# LightsDriver.net
KiCad netlist of a schematic drawn in Altium Designer
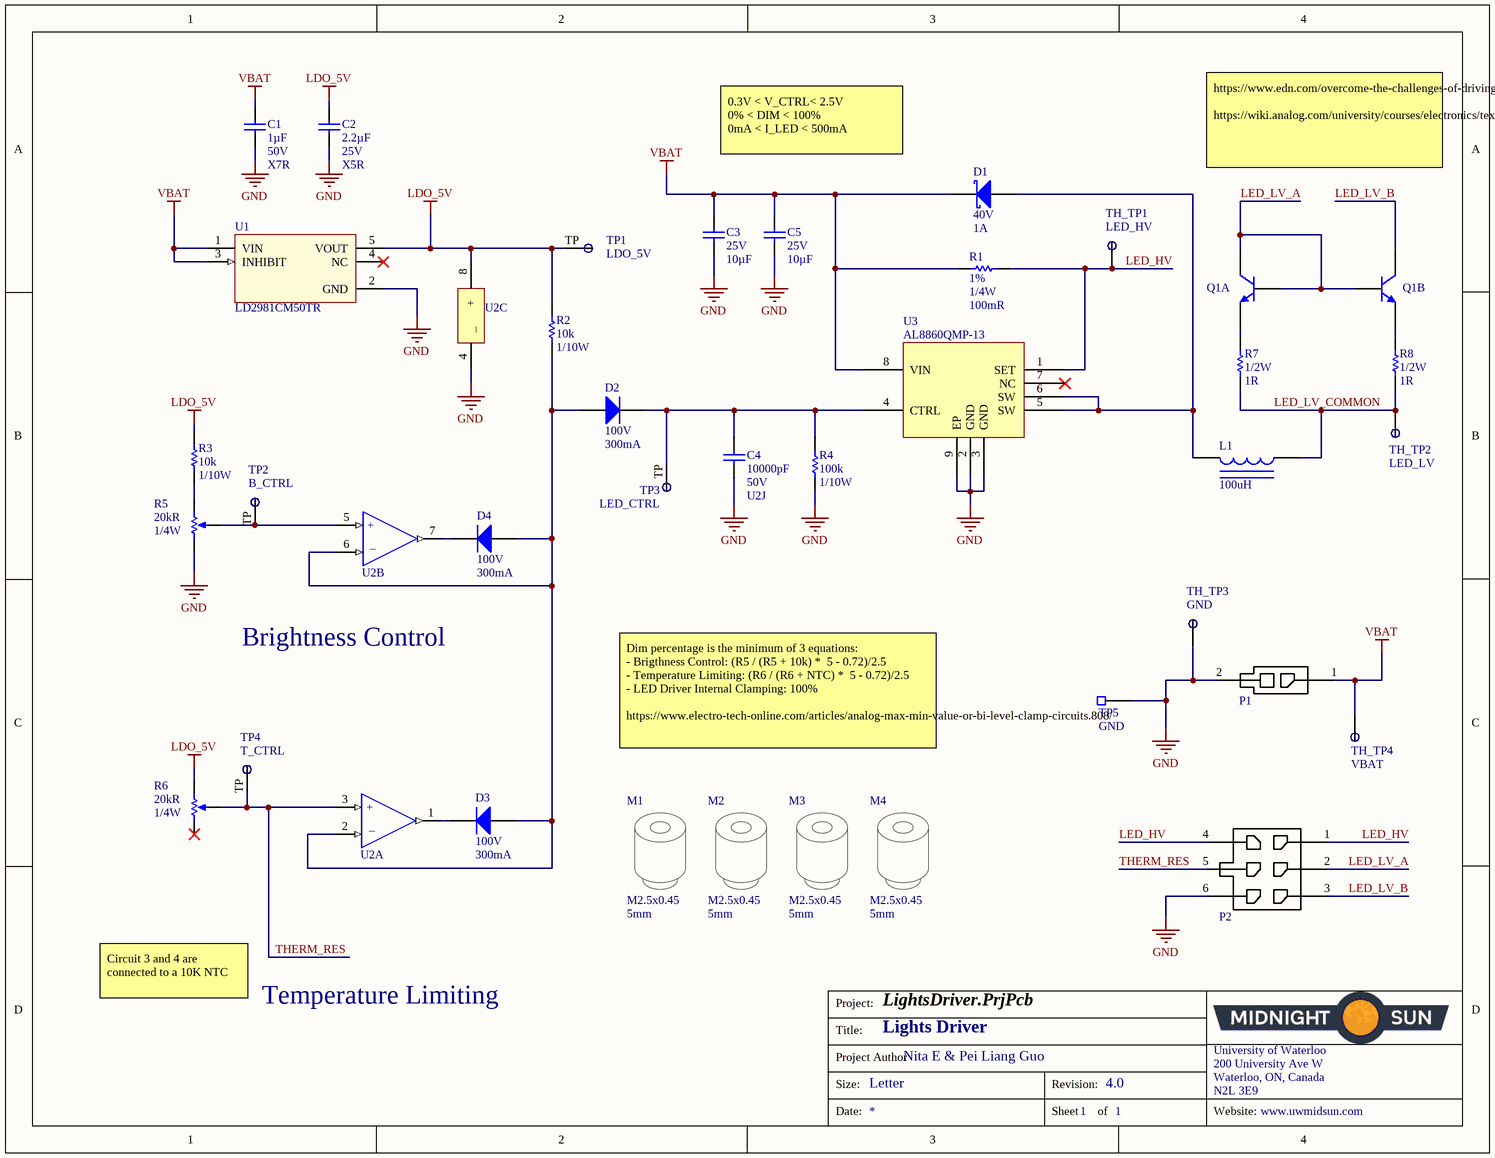
[diagram p0: LightsDriver.SchDoc]

(export (version "E")
  (design (tool "Eeschema 10.0.6"))
  (components
    (comp (ref "C1")
      (value "CAP CER 1UF 50V 10% X7R 0603")
      (footprint "CAP, 0603")
      (description "1µF ±10% 50V Ceramic Capacitor X7R 0603 (1608 Metric)")
      (fields
        (field (name "TOLERANCE") "±10%")
        (field (name "CAPACITANCE") "1µF")
        (field (name "VOLTAGE") "50V")
        (field (name "TEMPERATURE COEFFICIENT") "X7R")
      )
      (libsource (lib "Schematic Diagrams") (part "CAP CER 1UF 50V 10% X7R 0603"))
    )
    (comp (ref "C2")
      (value "CAP CER 2.2UF 25V 10% X5R 0603")
      (footprint "CAP, 0603")
      (description "2.2µF ±10% 25V Ceramic Capacitor X5R 0603 (1608 Metric)")
      (fields
        (field (name "TOLERANCE") "±10%")
        (field (name "CAPACITANCE") "2.2µF")
        (field (name "VOLTAGE") "25V")
        (field (name "TEMPERATURE COEFFICIENT") "X5R")
      )
      (libsource (lib "Schematic Diagrams") (part "CAP CER 2.2UF 25V 10% X5R 0603"))
    )
    (comp (ref "C3")
      (value "CAP CER 10uF 25V 10% X5R 0805")
      (footprint "CAP, 0805")
      (description "10µF ±10% 25V Ceramic Capacitor X5R 0805 (2012 Metric)")
      (fields
        (field (name "MANUFACTURER") "Murata Electronics North America")
        (field (name "MANUFACTURER PART NUMBER") "GRM21BR61E106KA73L")
        (field (name "VOLTAGE - RATED") "25V")
        (field (name "CAPACITANCE") "10µF")
      )
      (libsource (lib "Schematic Diagrams") (part "CAP CER 10uF 25V 10% X5R 0805"))
    )
    (comp (ref "C4")
      (value "CAP CER 10nF 50V 5% X7R 0603")
      (footprint "CAP, 0603")
      (description "10000pF ±5% 50V Ceramic Capacitor U2J 0603 (1608 Metric)")
      (fields
        (field (name "TOLERANCE") "±5%")
        (field (name "CAPACITANCE") "10000pF")
        (field (name "VOLTAGE") "50V")
        (field (name "TEMPERATURE COEFFICIENT") "U2J")
      )
      (libsource (lib "Schematic Diagrams") (part "CAP CER 10nF 50V 5% X7R 0603"))
    )
    (comp (ref "C5")
      (value "CAP CER 10uF 25V 10% X5R 0805")
      (footprint "CAP, 0805")
      (description "10µF ±10% 25V Ceramic Capacitor X5R 0805 (2012 Metric)")
      (fields
        (field (name "MANUFACTURER") "Murata Electronics North America")
        (field (name "MANUFACTURER PART NUMBER") "GRM21BR61E106KA73L")
        (field (name "VOLTAGE - RATED") "25V")
        (field (name "CAPACITANCE") "10µF")
      )
      (libsource (lib "Schematic Diagrams") (part "CAP CER 10uF 25V 10% X5R 0805"))
    )
    (comp (ref "D1")
      (value "DIODE SCHOTTKY 40V 1A SOD123F")
      (footprint "DIODE SOD123")
      (fields
        (field (name "MANUFACTURER") "ON Semiconductor / Fairchild")
        (field (name "MANUFACTURER PART NUMBER") "SS14FL")
        (field (name "MAX REVERSE VOLTAGE (DC)") "40V")
        (field (name "AVERAGE RECTIFIED CURRENT") "1A")
      )
      (libsource (lib "Schematic Diagrams") (part "DIODE SCHOTTKY 40V 1A SOD123F"))
    )
    (comp (ref "D2")
      (value "DIODE GEN PURP 100V 300MA SOD123")
      (footprint "DIODE GEN PURP 100V 300MA SOD123")
      (description "Diode Standard 100V 300mA (DC) Surface Mount SOD-123")
      (fields
        (field (name "MANUFACTURER") "Diodes Zetex")
        (field (name "MANUFACTURER PART NUMBER") "1N4148WQ-7-F")
        (field (name "MAX REPETITIVE REVERSE VOLTAGE (VRRM)") "100V")
        (field (name "FORWARD CURRENT") "300mA")
      )
      (libsource (lib "Schematic Diagrams") (part "DIODE GEN PURP 100V 300MA SOD123"))
    )
    (comp (ref "D3")
      (value "DIODE GEN PURP 100V 300MA SOD123")
      (footprint "DIODE GEN PURP 100V 300MA SOD123")
      (description "Diode Standard 100V 300mA (DC) Surface Mount SOD-123")
      (fields
        (field (name "MANUFACTURER") "Diodes Zetex")
        (field (name "MANUFACTURER PART NUMBER") "1N4148WQ-7-F")
        (field (name "MAX REPETITIVE REVERSE VOLTAGE (VRRM)") "100V")
        (field (name "FORWARD CURRENT") "300mA")
      )
      (libsource (lib "Schematic Diagrams") (part "DIODE GEN PURP 100V 300MA SOD123"))
    )
    (comp (ref "D4")
      (value "DIODE GEN PURP 100V 300MA SOD123")
      (footprint "DIODE GEN PURP 100V 300MA SOD123")
      (description "Diode Standard 100V 300mA (DC) Surface Mount SOD-123")
      (fields
        (field (name "MANUFACTURER") "Diodes Zetex")
        (field (name "MANUFACTURER PART NUMBER") "1N4148WQ-7-F")
        (field (name "MAX REPETITIVE REVERSE VOLTAGE (VRRM)") "100V")
        (field (name "FORWARD CURRENT") "300mA")
      )
      (libsource (lib "Schematic Diagrams") (part "DIODE GEN PURP 100V 300MA SOD123"))
    )
    (comp (ref "L1")
      (value "IND 100UH 1.2A 220MOHM SMD")
      (footprint "IND 100UH 1.2A 220MOHM SMD")
      (fields
        (field (name "MANUFACTURER") "Bourns")
        (field (name "MANUFACTURER PART NUMBER") "SRU1048A-101Y")
        (field (name "TOLERANCE") "30%")
        (field (name "INDUCTANCE") "100uH")
      )
      (libsource (lib "Schematic Diagrams") (part "IND 100UH 1.2A 220MOHM SMD"))
    )
    (comp (ref "M1")
      (value "STANDOFF RND M2.5X0.45 STEEL 5MM")
      (footprint "M2.5 Standoff")
      (fields
        (field (name "MANUFACTURER") "Wurth Electronics")
        (field (name "MANUFACTURER PART NUMBER") "9774050151R")
        (field (name "SCREW-THREAD SIZE") "M2.5x0.45")
        (field (name "STANDOFF HEIGHT") "5mm")
      )
      (libsource (lib "Schematic Diagrams") (part "STANDOFF RND M2.5X0.45 STEEL 5MM"))
    )
    (comp (ref "M2")
      (value "STANDOFF RND M2.5X0.45 STEEL 5MM")
      (footprint "M2.5 Standoff")
      (fields
        (field (name "MANUFACTURER") "Wurth Electronics")
        (field (name "MANUFACTURER PART NUMBER") "9774050151R")
        (field (name "SCREW-THREAD SIZE") "M2.5x0.45")
        (field (name "STANDOFF HEIGHT") "5mm")
      )
      (libsource (lib "Schematic Diagrams") (part "STANDOFF RND M2.5X0.45 STEEL 5MM"))
    )
    (comp (ref "M3")
      (value "STANDOFF RND M2.5X0.45 STEEL 5MM")
      (footprint "M2.5 Standoff")
      (fields
        (field (name "MANUFACTURER") "Wurth Electronics")
        (field (name "MANUFACTURER PART NUMBER") "9774050151R")
        (field (name "SCREW-THREAD SIZE") "M2.5x0.45")
        (field (name "STANDOFF HEIGHT") "5mm")
      )
      (libsource (lib "Schematic Diagrams") (part "STANDOFF RND M2.5X0.45 STEEL 5MM"))
    )
    (comp (ref "M4")
      (value "STANDOFF RND M2.5X0.45 STEEL 5MM")
      (footprint "M2.5 Standoff")
      (fields
        (field (name "MANUFACTURER") "Wurth Electronics")
        (field (name "MANUFACTURER PART NUMBER") "9774050151R")
        (field (name "SCREW-THREAD SIZE") "M2.5x0.45")
        (field (name "STANDOFF HEIGHT") "5mm")
      )
      (libsource (lib "Schematic Diagrams") (part "STANDOFF RND M2.5X0.45 STEEL 5MM"))
    )
    (comp (ref "P1")
      (value "TO PWR DISTR")
      (footprint "CONN, 2POS MICRO-FIT R/A 2ROW")
      (description "Header Connector, Pcb Mount, Recept, 2 Contacts, Pin, 0.118 Pitch, R Angle Pc Tail Terminal")
      (fields (field (name "MANUFACTURER") "Molex") (field (name "MANUFACTURER PART NUMBER") "43045-0221"))
      (libsource (lib "Schematic Diagrams") (part "CONN 2POS MICRO-FIT R/A 2ROW 3mm"))
    )
    (comp (ref "P2")
      (value "CONN 6POS MICRO-FIT R/A 2ROW 3mm")
      (footprint "CONN, 6POS MICRO-FIT R/A 2ROW")
      (description "Conn Wire to Board HDR 6 POS 3mm Solder RA Thru-Hole Micro-Fit 3.0™ Tray")
      (fields (field (name "MANUFACTURER") "Molex") (field (name "MANUFACTURER PART NUMBER") "043045-0621"))
      (libsource (lib "Schematic Diagrams") (part "CONN 6POS MICRO-FIT R/A 2ROW 3mm"))
    )
    (comp (ref "Q1")
      (value "BJT NPN DUAL 80V 1A 6-TSOP")
      (footprint "TSOP6 (SOT457)")
      (description "Bipolar (BJT) Transistor Array 2 PNP (Dual) Matched Pair 80V 1A 140MHz 500mW Surface Mount 6-TSOP")
      (fields (field (name "MANUFACTURER") "Nexperia") (field (name "MANUFACTURER PART NUMBER") "BCM56DSF"))
      (libsource (lib "Schematic Diagrams") (part "BJT NPN DUAL 80V 1A 6-TSOP"))
    )
    (comp (ref "R1")
      (value "RES 0.1 OHM 1% 1/4W 1206")
      (footprint "RES 1206")
      (description "Res Thick Film 1206 0.1 Ohm 1% 0.25W(1/4W) ±600ppm/C Molded SMD Paper T/R")
      (fields
        (field (name "MANUFACTURER") "Yageo")
        (field (name "MANUFACTURER PART NUMBER") "RL1206FR-070R1L")
        (field (name "TOLERANCE") "1%")
        (field (name "POWER RATING") "1/4W")
        (field (name "RESISTANCE") "100mR")
      )
      (libsource (lib "Schematic Diagrams") (part "RES 0.1 OHM 1% 1/4W 1206"))
    )
    (comp (ref "R2")
      (value "RES 10K OHM 1% 1/10W 0603")
      (footprint "RES, 0603")
      (description "RES SMD 10K OHM 1% 1/10W 0603")
      (fields
        (field (name "TOLERANCE") "±1%")
        (field (name "RESISTANCE") "10k")
        (field (name "POWER") "1/10W")
      )
      (libsource (lib "Schematic Diagrams") (part "RES 10K OHM 1% 1/10W 0603"))
    )
    (comp (ref "R3")
      (value "RES 10K OHM 1% 1/10W 0603")
      (footprint "RES, 0603")
      (description "RES SMD 10K OHM 1% 1/10W 0603")
      (fields
        (field (name "TOLERANCE") "±1%")
        (field (name "RESISTANCE") "10k")
        (field (name "POWER") "1/10W")
      )
      (libsource (lib "Schematic Diagrams") (part "RES 10K OHM 1% 1/10W 0603"))
    )
    (comp (ref "R4")
      (value "RES 100K OHM 5% 1/8W 0603")
      (footprint "RES, 0603")
      (description "RES SMD 100K OHM 5% 1/10W 0603")
      (fields
        (field (name "TOLERANCE") "±5%")
        (field (name "RESISTANCE") "100k")
        (field (name "POWER") "1/10W")
      )
      (libsource (lib "Schematic Diagrams") (part "RES 100K OHM 5% 1/8W 0603"))
    )
    (comp (ref "R5")
      (value "POT 20k OHM 20% 1/4W SMD")
      (footprint "POT TRIMMER 20K")
      (description "20 kOhms 0.25W, 1/4W Gull Wing Surface Mount Trimmer Potentiometer Cermet 1 Turn Top Adjustment")
      (fields
        (field (name "MANUFACTURER") "TT BI")
        (field (name "MANUFACTURER PART NUMBER") "23BR20KLFTR")
        (field (name "RESISTANCE") "20kR")
        (field (name "POWER RATING") "1/4W")
      )
      (libsource (lib "Schematic Diagrams") (part "POT 20k OHM 20% 1/4W SMD"))
    )
    (comp (ref "R6")
      (value "POT 20k OHM 20% 1/4W SMD")
      (footprint "POT TRIMMER 20K")
      (description "20 kOhms 0.25W, 1/4W Gull Wing Surface Mount Trimmer Potentiometer Cermet 1 Turn Top Adjustment")
      (fields
        (field (name "MANUFACTURER") "TT BI")
        (field (name "MANUFACTURER PART NUMBER") "23BR20KLFTR")
        (field (name "RESISTANCE") "20kR")
        (field (name "POWER RATING") "1/4W")
      )
      (libsource (lib "Schematic Diagrams") (part "POT 20k OHM 20% 1/4W SMD"))
    )
    (comp (ref "R7")
      (value "RES 1 OHM 1% 1/2W 1206")
      (footprint "RES 1206")
      (description "BOURNS - CRM1206AFX-1R00ELF - RES, 1R, 1%, 1206, THICK FILM")
      (fields
        (field (name "MANUFACTURER") "Bourns")
        (field (name "MANUFACTURER PART NUMBER") "CRM1206AFX-1R00ELF")
        (field (name "MAX POWER DISSIPATION") "1/2W")
        (field (name "RESISTANCE") "1R")
      )
      (libsource (lib "Schematic Diagrams") (part "RES 1 OHM 1% 1/2W 1206"))
    )
    (comp (ref "R8")
      (value "RES 1 OHM 1% 1/2W 1206")
      (footprint "RES 1206")
      (description "BOURNS - CRM1206AFX-1R00ELF - RES, 1R, 1%, 1206, THICK FILM")
      (fields
        (field (name "MANUFACTURER") "Bourns")
        (field (name "MANUFACTURER PART NUMBER") "CRM1206AFX-1R00ELF")
        (field (name "MAX POWER DISSIPATION") "1/2W")
        (field (name "RESISTANCE") "1R")
      )
      (libsource (lib "Schematic Diagrams") (part "RES 1 OHM 1% 1/2W 1206"))
    )
    (comp (ref "TH_TP1")
      (value "LED_HV")
      (footprint "Thru Test Point")
      (libsource (lib "Schematic Diagrams") (part "Thru Test Point"))
    )
    (comp (ref "TH_TP2")
      (value "LED_LV")
      (footprint "Thru Test Point")
      (libsource (lib "Schematic Diagrams") (part "Thru Test Point"))
    )
    (comp (ref "TH_TP3")
      (value "GND")
      (footprint "Thru Test Point")
      (libsource (lib "Schematic Diagrams") (part "Thru Test Point"))
    )
    (comp (ref "TH_TP4")
      (value "VBAT")
      (footprint "Thru Test Point")
      (libsource (lib "Schematic Diagrams") (part "Thru Test Point"))
    )
    (comp (ref "TP1")
      (value "LDO_5V")
      (footprint "Test Point")
      (libsource (lib "Schematic Diagrams") (part "Test Point"))
    )
    (comp (ref "TP2")
      (value "B_CTRL")
      (footprint "Test Point")
      (libsource (lib "Schematic Diagrams") (part "Test Point"))
    )
    (comp (ref "TP3")
      (value "LED_CTRL")
      (footprint "Test Point")
      (libsource (lib "Schematic Diagrams") (part "Test Point"))
    )
    (comp (ref "TP4")
      (value "T_CTRL")
      (footprint "Test Point")
      (libsource (lib "Schematic Diagrams") (part "Test Point"))
    )
    (comp (ref "TP5")
      (value "GND")
      (footprint "TEST POINT 0603 SMD")
      (libsource (lib "Schematic Diagrams") (part "Test Point 0603 SMD"))
    )
    (comp (ref "U1")
      (value "IC REG LDO 5V 0.1A SOT23-5")
      (footprint "SOT95P280X145-5N")
      (description "Linear Voltage Regulator IC Positive Fixed Output 5V 100mA SOT-23-5")
      (fields (field (name "MANUFACTURER PART NUMBER 1") "LD2981CM50TR"))
      (libsource (lib "Schematic Diagrams") (part "IC REG LDO 5V 0.1A SOT23-5"))
    )
    (comp (ref "U2")
      (value "IC OP AMP DUAL GP RR 10MHZ 8-VSSOP")
      (footprint "IC OP AMP DUAL 8-VSSOP")
      (description "General Purpose Amplifier 2 Circuit Rail-to-Rail 8-VSSOP")
      (fields
        (field (name "MANUFACTURER") "Texas Instruments")
        (field (name "MANUFACTURER PART NUMBER") "OPA2197IDGKR")
      )
      (libsource (lib "Schematic Diagrams") (part "IC OP AMP DUAL GP RR 10MHZ 8-VSSOP"))
    )
    (comp (ref "U3")
      (value "IC LED DRIVER AL8860Q MSOP-8EP")
      (footprint "IC LED DRIVER AL8860Q 8-MSOP-EP")
      (description "AL8860 Series 40 V 1.5 A SMT High Efficiency Buck LED Driver - MSOP-8EP")
      (fields (field (name "MANUFACTURER") "Diodes") (field (name "MANUFACTURER PART NUMBER") "AL8860QMP-13"))
      (libsource (lib "Schematic Diagrams") (part "IC LED DRIVER AL8860Q MSOP-8EP"))
    )
  )
  (nets
    (net (code "1") (name "/LED_HV") (class "Default")
      (node (ref "P2") (pin "1") (pinfunction "1_1") (pintype "passive"))
      (node (ref "P2") (pin "4") (pinfunction "4_4") (pintype "passive"))
      (node (ref "R1") (pin "2") (pinfunction "2_2") (pintype "passive"))
      (node (ref "TH_TP1") (pin "TH_TP") (pinfunction "1_TH_TP") (pintype "passive"))
      (node (ref "U3") (pin "1") (pinfunction "SET_1") (pintype "passive"))
    )
    (net (code "2") (name "/LED_LV_A") (class "Default")
      (node (ref "P2") (pin "2") (pinfunction "2_2") (pintype "passive"))
      (node (ref "Q1") (pin "1") (pinfunction "B1_1") (pintype "passive"))
      (node (ref "Q1") (pin "2") (pinfunction "B2_2") (pintype "passive"))
      (node (ref "Q1") (pin "6") (pinfunction "C1_6") (pintype "passive"))
    )
    (net (code "3") (name "/LED_LV_B") (class "Default")
      (node (ref "P2") (pin "3") (pinfunction "3_3") (pintype "passive"))
      (node (ref "Q1") (pin "3") (pinfunction "C2_3") (pintype "passive"))
    )
    (net (code "4") (name "/LED_LV_COMMON") (class "Default")
      (node (ref "L1") (pin "1") (pinfunction "1_1") (pintype "passive"))
      (node (ref "R7") (pin "2") (pinfunction "2_2") (pintype "passive"))
      (node (ref "R8") (pin "2") (pinfunction "2_2") (pintype "passive"))
      (node (ref "TH_TP2") (pin "TH_TP") (pinfunction "1_TH_TP") (pintype "passive"))
    )
    (net (code "5") (name "/THERM_RES") (class "Default")
      (node (ref "P2") (pin "5") (pinfunction "5_5") (pintype "passive"))
      (node (ref "R6") (pin "2") (pinfunction "TAP_2") (pintype "passive"))
      (node (ref "TP4") (pin "TP") (pinfunction "1_TP") (pintype "passive"))
      (node (ref "U2") (pin "3") (pinfunction "+IN_A_3") (pintype "input"))
    )
    (net (code "6") (name "GND") (class "Default")
      (node (ref "C1") (pin "2") (pinfunction "2_2") (pintype "passive"))
      (node (ref "C2") (pin "2") (pinfunction "2_2") (pintype "passive"))
      (node (ref "C3") (pin "2") (pinfunction "2_2") (pintype "passive"))
      (node (ref "C4") (pin "2") (pinfunction "2_2") (pintype "passive"))
      (node (ref "C5") (pin "2") (pinfunction "2_2") (pintype "passive"))
      (node (ref "P1") (pin "2") (pinfunction "2_2") (pintype "passive"))
      (node (ref "P2") (pin "6") (pinfunction "6_6") (pintype "passive"))
      (node (ref "R4") (pin "2") (pinfunction "2_2") (pintype "passive"))
      (node (ref "R5") (pin "1") (pinfunction "TOP_1") (pintype "passive"))
      (node (ref "TH_TP3") (pin "TH_TP") (pinfunction "1_TH_TP") (pintype "passive"))
      (node (ref "TP5") (pin "1") (pinfunction "1_1") (pintype "passive"))
      (node (ref "U1") (pin "2") (pinfunction "GND_2") (pintype "power_in"))
      (node (ref "U2") (pin "4") (pinfunction "__4") (pintype "power_in"))
      (node (ref "U3") (pin "2") (pinfunction "GND_2") (pintype "power_in"))
      (node (ref "U3") (pin "3") (pinfunction "GND_3") (pintype "power_in"))
      (node (ref "U3") (pin "9") (pinfunction "EP_9") (pintype "power_in"))
    )
    (net (code "7") (name "LDO_5V") (class "Default")
      (node (ref "C2") (pin "1") (pinfunction "1_1") (pintype "passive"))
      (node (ref "R2") (pin "1") (pinfunction "1_1") (pintype "passive"))
      (node (ref "R3") (pin "1") (pinfunction "1_1") (pintype "passive"))
      (node (ref "R6") (pin "3") (pinfunction "BOT_3") (pintype "passive"))
      (node (ref "TP1") (pin "TP") (pinfunction "1_TP") (pintype "passive"))
      (node (ref "U1") (pin "5") (pinfunction "VOUT_5") (pintype "power_in"))
      (node (ref "U2") (pin "8") (pinfunction "+_8") (pintype "power_in"))
    )
    (net (code "8") (name "Net-(D1-Pad2)") (class "Default")
      (node (ref "D1") (pin "2") (pinfunction "2_2") (pintype "passive"))
      (node (ref "L1") (pin "2") (pinfunction "2_2") (pintype "passive"))
      (node (ref "U3") (pin "5") (pinfunction "SW_5") (pintype "passive"))
      (node (ref "U3") (pin "6") (pinfunction "SW_6") (pintype "passive"))
    )
    (net (code "9") (name "Net-(D2-ANODE)") (class "Default")
      (node (ref "D2") (pin "2") (pinfunction "ANODE_2") (pintype "passive"))
      (node (ref "D3") (pin "2") (pinfunction "ANODE_2") (pintype "passive"))
      (node (ref "D4") (pin "2") (pinfunction "ANODE_2") (pintype "passive"))
      (node (ref "R2") (pin "2") (pinfunction "2_2") (pintype "passive"))
      (node (ref "U2") (pin "2") (pinfunction "-IN_A_2") (pintype "input"))
      (node (ref "U2") (pin "6") (pinfunction "-IN_B_6") (pintype "input"))
    )
    (net (code "10") (name "Net-(D2-CATHODE)") (class "Default")
      (node (ref "C4") (pin "1") (pinfunction "1_1") (pintype "passive"))
      (node (ref "D2") (pin "1") (pinfunction "CATHODE_1") (pintype "passive"))
      (node (ref "R4") (pin "1") (pinfunction "1_1") (pintype "passive"))
      (node (ref "TP3") (pin "TP") (pinfunction "1_TP") (pintype "passive"))
      (node (ref "U3") (pin "4") (pinfunction "CTRL_4") (pintype "passive"))
    )
    (net (code "11") (name "Net-(D3-CATHODE)") (class "Default")
      (node (ref "D3") (pin "1") (pinfunction "CATHODE_1") (pintype "passive"))
      (node (ref "U2") (pin "1") (pinfunction "OUT_A_1") (pintype "output"))
    )
    (net (code "12") (name "Net-(D4-CATHODE)") (class "Default")
      (node (ref "D4") (pin "1") (pinfunction "CATHODE_1") (pintype "passive"))
      (node (ref "U2") (pin "7") (pinfunction "OUT_B_7") (pintype "output"))
    )
    (net (code "13") (name "Net-(Q1A-E1)") (class "Default")
      (node (ref "Q1") (pin "5") (pinfunction "E1_5") (pintype "passive"))
      (node (ref "R7") (pin "1") (pinfunction "1_1") (pintype "passive"))
    )
    (net (code "14") (name "Net-(Q1B-E2)") (class "Default")
      (node (ref "Q1") (pin "4") (pinfunction "E2_4") (pintype "passive"))
      (node (ref "R8") (pin "1") (pinfunction "1_1") (pintype "passive"))
    )
    (net (code "15") (name "Net-(R5-BOT)") (class "Default")
      (node (ref "R3") (pin "2") (pinfunction "2_2") (pintype "passive"))
      (node (ref "R5") (pin "3") (pinfunction "BOT_3") (pintype "passive"))
    )
    (net (code "16") (name "Net-(R5-TAP)") (class "Default")
      (node (ref "R5") (pin "2") (pinfunction "TAP_2") (pintype "passive"))
      (node (ref "TP2") (pin "TP") (pinfunction "1_TP") (pintype "passive"))
      (node (ref "U2") (pin "5") (pinfunction "+IN_B_5") (pintype "input"))
    )
    (net (code "17") (name "VBAT") (class "Default")
      (node (ref "C1") (pin "1") (pinfunction "1_1") (pintype "passive"))
      (node (ref "C3") (pin "1") (pinfunction "1_1") (pintype "passive"))
      (node (ref "C5") (pin "1") (pinfunction "1_1") (pintype "passive"))
      (node (ref "D1") (pin "1") (pinfunction "1_1") (pintype "passive"))
      (node (ref "P1") (pin "1") (pinfunction "1_1") (pintype "passive"))
      (node (ref "R1") (pin "1") (pinfunction "1_1") (pintype "passive"))
      (node (ref "TH_TP4") (pin "TH_TP") (pinfunction "1_TH_TP") (pintype "passive"))
      (node (ref "U1") (pin "1") (pinfunction "VIN_1") (pintype "power_in"))
      (node (ref "U1") (pin "3") (pinfunction "INHIBIT_3") (pintype "input"))
      (node (ref "U3") (pin "8") (pinfunction "VIN_8") (pintype "power_in"))
    )
    (net (code "18") (name "unconnected-(R6-TOP-Pad1)") (class "Default")
      (node (ref "R6") (pin "1") (pinfunction "TOP_1") (pintype "passive+no_connect"))
    )
    (net (code "19") (name "unconnected-(U1-NC-Pad4)") (class "Default")
      (node (ref "U1") (pin "4") (pinfunction "NC_4") (pintype "passive+no_connect"))
    )
    (net (code "20") (name "unconnected-(U3-NC-Pad7)") (class "Default")
      (node (ref "U3") (pin "7") (pinfunction "NC_7") (pintype "passive+no_connect"))
    )
  )
)
